# knxhome-lqfp48.net
KiCad netlist of a schematic drawn in EAGLE
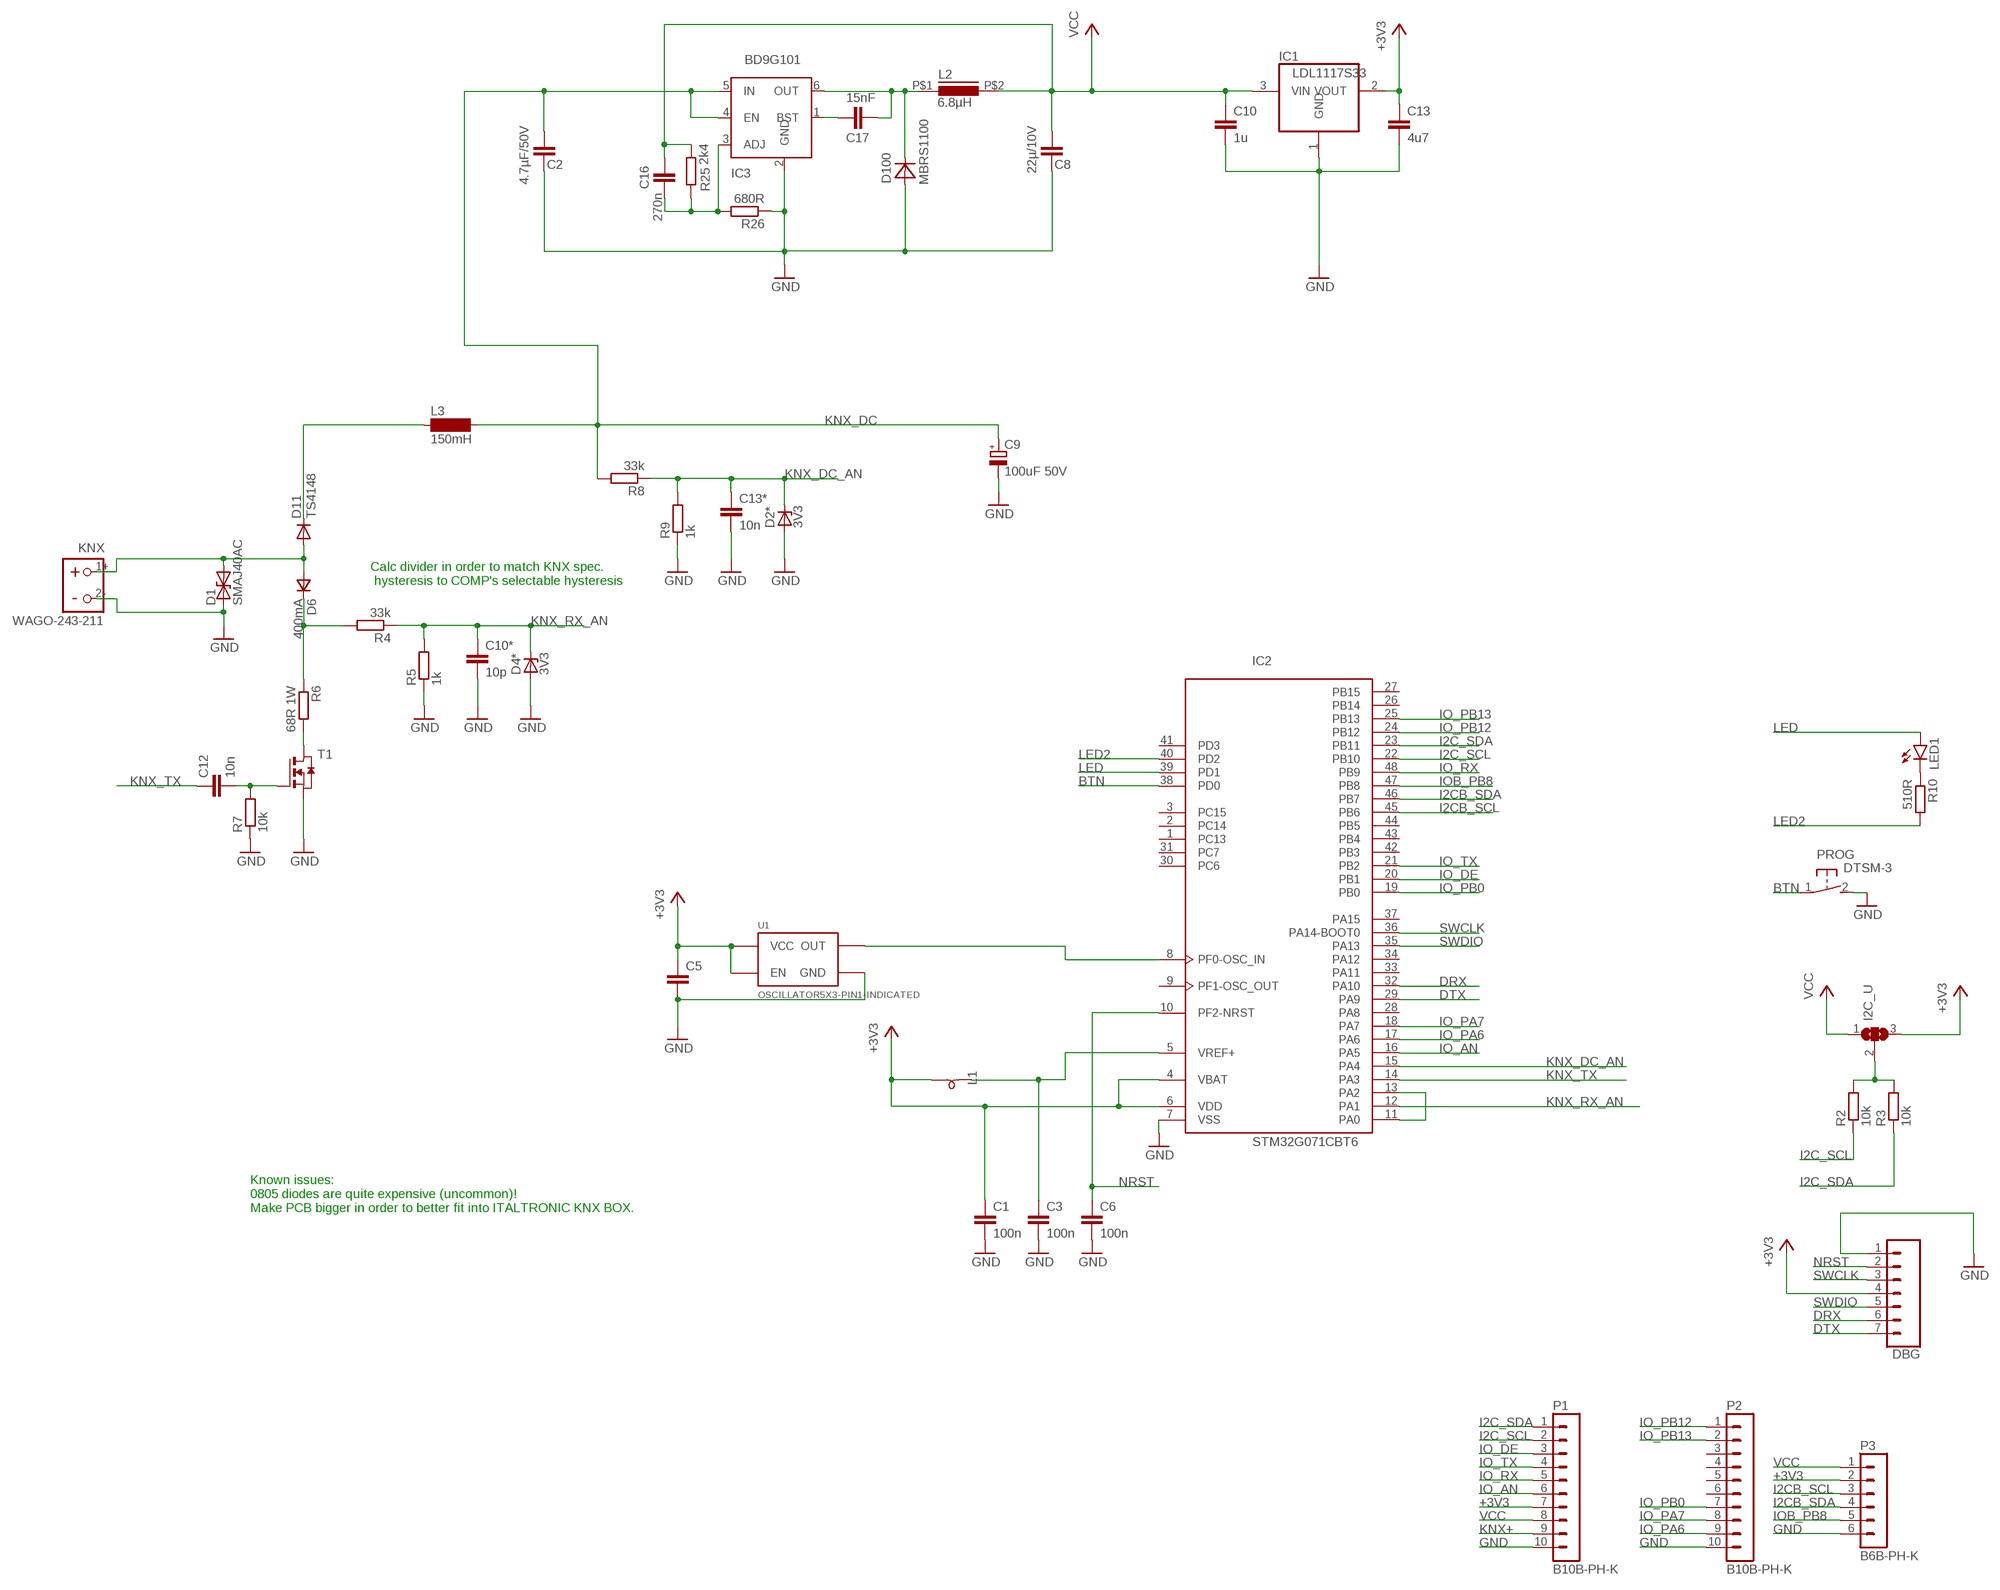
[diagram p0: schematic, sheet 1]

(export (version "E")
  (design (tool "Eeschema 10.0.6"))
  (components
    (comp (ref "C1")
      (value "100n")
      (footprint "eagle-import:C0805")
      (libsource (lib "eagle-import") (part "C-EUC0805"))
    )
    (comp (ref "C2")
      (value "4.7µF/50V")
      (footprint "eagle-import:C0805")
      (libsource (lib "eagle-import") (part "C-EUC0805"))
    )
    (comp (ref "C3")
      (value "100n")
      (footprint "eagle-import:C0805")
      (libsource (lib "eagle-import") (part "C-EUC0805"))
    )
    (comp (ref "C5")
      (value "C-EUC0805")
      (footprint "eagle-import:C0805")
      (libsource (lib "eagle-import") (part "C-EUC0805"))
    )
    (comp (ref "C6")
      (value "100n")
      (footprint "eagle-import:C0805")
      (libsource (lib "eagle-import") (part "C-EUC0805"))
    )
    (comp (ref "C8")
      (value "22µ/10V")
      (footprint "eagle-import:C0805")
      (libsource (lib "eagle-import") (part "C-EUC0805"))
    )
    (comp (ref "C9")
      (value "100uF 50V")
      (footprint "eagle-import:E3,5-8")
      (libsource (lib "eagle-import") (part "CPOL-EUE3.5-8"))
    )
    (comp (ref "C10")
      (value "1u")
      (footprint "eagle-import:C0805")
      (libsource (lib "eagle-import") (part "C-EUC0805"))
    )
    (comp (ref "C10*")
      (value "10p")
      (footprint "eagle-import:C0805")
      (libsource (lib "eagle-import") (part "C-EUC0805"))
    )
    (comp (ref "C12")
      (value "10n")
      (footprint "eagle-import:C0805")
      (libsource (lib "eagle-import") (part "C-EUC0805"))
    )
    (comp (ref "C13")
      (value "4u7")
      (footprint "eagle-import:C0805")
      (libsource (lib "eagle-import") (part "C-EUC0805"))
    )
    (comp (ref "C13*")
      (value "10n")
      (footprint "eagle-import:C0805")
      (libsource (lib "eagle-import") (part "C-EUC0805"))
    )
    (comp (ref "C16")
      (value "270n")
      (footprint "eagle-import:C0805")
      (libsource (lib "eagle-import") (part "C-EUC0805"))
    )
    (comp (ref "C17")
      (value "15nF")
      (footprint "eagle-import:C0805")
      (libsource (lib "eagle-import") (part "C-EUC0805"))
    )
    (comp (ref "D1")
      (value "SMAJ40AC")
      (footprint "eagle-import:DO-214AC")
      (libsource (lib "eagle-import") (part "SMAJ40AC"))
    )
    (comp (ref "D2*")
      (value "3V3")
      (footprint "eagle-import:SOT23")
      (libsource (lib "eagle-import") (part "ZENER-DIODESOT23"))
    )
    (comp (ref "D4*")
      (value "3V3")
      (footprint "eagle-import:SOT23")
      (libsource (lib "eagle-import") (part "ZENER-DIODESOT23"))
    )
    (comp (ref "D6")
      (value "400mA")
      (footprint "eagle-import:SOD323")
      (fields (field (name "MPN") "CDSOD323-T05C"))
      (libsource (lib "eagle-import") (part "DSOD323"))
    )
    (comp (ref "D11")
      (value "TS4148")
      (footprint "eagle-import:D0805")
      (libsource (lib "eagle-import") (part "DIODE-D0805"))
    )
    (comp (ref "D100")
      (value "MBRS1100")
      (footprint "eagle-import:SMA")
      (libsource (lib "eagle-import") (part "MBRA340T3"))
    )
    (comp (ref "DBG")
      (value "CONN_07LOCK")
      (footprint "eagle-import:1X07_LOCK")
      (libsource (lib "eagle-import") (part "CONN_07LOCK"))
    )
    (comp (ref "I2C_U")
      (value "SJ2W")
      (footprint "eagle-import:SJ_2")
      (libsource (lib "eagle-import") (part "SJ2W"))
    )
    (comp (ref "IC1")
      (value "LDL1117S33")
      (footprint "eagle-import:SOT223")
      (fields (field (name "MPN") "REG1117"))
      (libsource (lib "eagle-import") (part "REG1117"))
    )
    (comp (ref "IC2")
      (value "STM32G071CBT6")
      (footprint "eagle-import:LQFP48")
      (libsource (lib "eagle-import") (part "STM32G071CBT6"))
    )
    (comp (ref "IC3")
      (value "BD9G101")
      (footprint "eagle-import:SOT23-6")
      (libsource (lib "eagle-import") (part "BD9G101GBD9G101G-SOT23-6"))
    )
    (comp (ref "KNX")
      (value "WAGO-243-211")
      (footprint "eagle-import:WAGO-243-211")
      (libsource (lib "eagle-import") (part "WAGO-243-211"))
    )
    (comp (ref "L1")
      (value "FERRITE BEAD")
      (footprint "eagle-import:SM-B5")
      (libsource (lib "eagle-import") (part "SM-B5"))
    )
    (comp (ref "L2")
      (value "6.8µH")
      (footprint "eagle-import:PIS2812")
      (libsource (lib "eagle-import") (part "IND_FASTRON_1616FPS"))
    )
    (comp (ref "L3")
      (value "150mH")
      (footprint "eagle-import:BS11_LIEGEND")
      (libsource (lib "eagle-import") (part "SD12BS11_LIEGEND"))
    )
    (comp (ref "LED1")
      (value "LEDCHIP-LED0805")
      (footprint "eagle-import:CHIP-LED0805")
      (libsource (lib "eagle-import") (part "LEDCHIP-LED0805"))
    )
    (comp (ref "P1")
      (value "B10B-PH-K")
      (footprint "eagle-import:B10B-PH-K")
      (libsource (lib "eagle-import") (part "B10B-PH-K"))
    )
    (comp (ref "P2")
      (value "B10B-PH-K")
      (footprint "eagle-import:B10B-PH-K")
      (libsource (lib "eagle-import") (part "B10B-PH-K"))
    )
    (comp (ref "P3")
      (value "B6B-PH-K")
      (footprint "eagle-import:B6B-PH-K")
      (libsource (lib "eagle-import") (part "B6B-PH-K"))
    )
    (comp (ref "PROG")
      (value "DTSM-3")
      (footprint "eagle-import:DTSM-3")
      (libsource (lib "eagle-import") (part "DTSM-3"))
    )
    (comp (ref "R2")
      (value "10k")
      (footprint "eagle-import:R0805")
      (libsource (lib "eagle-import") (part "R-EU_R0805"))
    )
    (comp (ref "R3")
      (value "10k")
      (footprint "eagle-import:R0805")
      (libsource (lib "eagle-import") (part "R-EU_R0805"))
    )
    (comp (ref "R4")
      (value "33k")
      (footprint "eagle-import:R0805")
      (libsource (lib "eagle-import") (part "R-EU_R0805"))
    )
    (comp (ref "R5")
      (value "1k")
      (footprint "eagle-import:R0805")
      (libsource (lib "eagle-import") (part "R-EU_R0805"))
    )
    (comp (ref "R6")
      (value "68R 1W")
      (footprint "eagle-import:R2512")
      (libsource (lib "eagle-import") (part "R-EU_R2512"))
    )
    (comp (ref "R7")
      (value "10k")
      (footprint "eagle-import:R0805")
      (libsource (lib "eagle-import") (part "R-EU_R0805"))
    )
    (comp (ref "R8")
      (value "33k")
      (footprint "eagle-import:R0805")
      (libsource (lib "eagle-import") (part "R-EU_R0805"))
    )
    (comp (ref "R9")
      (value "1k")
      (footprint "eagle-import:R0805")
      (libsource (lib "eagle-import") (part "R-EU_R0805"))
    )
    (comp (ref "R10")
      (value "510R")
      (footprint "eagle-import:R0805")
      (libsource (lib "eagle-import") (part "R-EU_R0805"))
    )
    (comp (ref "R25")
      (value "2k4")
      (footprint "eagle-import:R0805")
      (libsource (lib "eagle-import") (part "R-EU_R0805"))
    )
    (comp (ref "R26")
      (value "680R")
      (footprint "eagle-import:R0805")
      (libsource (lib "eagle-import") (part "R-EU_R0805"))
    )
    (comp (ref "T1")
      (value "NMOSSOT23")
      (footprint "eagle-import:SOT-23")
      (libsource (lib "eagle-import") (part "NMOSSOT23"))
    )
    (comp (ref "U1")
      (value "OSCILLATOR5X3-PIN1-INDICATED")
      (footprint "eagle-import:CRYSTAL-OSC-SMD-5X3")
      (libsource (lib "eagle-import") (part "OSCILLATOR5X3-PIN1-INDICATED"))
    )
  )
  (nets
    (net (code "1") (name "+3V3") (class "Default")
      (node (ref "C1") (pin "1") (pinfunction "1_1") (pintype "passive"))
      (node (ref "C13") (pin "1") (pinfunction "1_1") (pintype "passive"))
      (node (ref "C5") (pin "1") (pinfunction "1_1") (pintype "passive"))
      (node (ref "DBG") (pin "4") (pinfunction "4_4") (pintype "passive"))
      (node (ref "I2C_U") (pin "3") (pinfunction "3_3") (pintype "passive"))
      (node (ref "IC1") (pin "2") (pinfunction "VOUT_2") (pintype "output"))
      (node (ref "IC2") (pin "4") (pinfunction "VBAT_4") (pintype "power_in"))
      (node (ref "IC2") (pin "6") (pinfunction "VDD_6") (pintype "power_in"))
      (node (ref "L1") (pin "1") (pinfunction "1_1") (pintype "passive"))
      (node (ref "P1") (pin "7") (pinfunction "7_7") (pintype "passive"))
      (node (ref "P3") (pin "2") (pinfunction "2_2") (pintype "passive"))
      (node (ref "U1") (pin "1") (pinfunction "EN_1") (pintype "bidirectional"))
      (node (ref "U1") (pin "4") (pinfunction "VCC_4") (pintype "bidirectional"))
    )
    (net (code "2") (name "/BTN") (class "Default")
      (node (ref "IC2") (pin "38") (pinfunction "PD0_38") (pintype "bidirectional"))
      (node (ref "PROG") (pin "1") (pinfunction "1_1") (pintype "passive"))
    )
    (net (code "3") (name "/DRX") (class "Default")
      (node (ref "DBG") (pin "6") (pinfunction "6_6") (pintype "passive"))
      (node (ref "IC2") (pin "32") (pinfunction "PA10_32") (pintype "bidirectional"))
    )
    (net (code "4") (name "/DTX") (class "Default")
      (node (ref "DBG") (pin "7") (pinfunction "7_7") (pintype "passive"))
      (node (ref "IC2") (pin "29") (pinfunction "PA9_29") (pintype "bidirectional"))
    )
    (net (code "5") (name "/I2CB_SCL") (class "Default")
      (node (ref "IC2") (pin "45") (pinfunction "PB6_45") (pintype "bidirectional"))
      (node (ref "P3") (pin "3") (pinfunction "3_3") (pintype "passive"))
    )
    (net (code "6") (name "/I2CB_SDA") (class "Default")
      (node (ref "IC2") (pin "46") (pinfunction "PB7_46") (pintype "bidirectional"))
      (node (ref "P3") (pin "4") (pinfunction "4_4") (pintype "passive"))
    )
    (net (code "7") (name "/I2C_SCL") (class "Default")
      (node (ref "IC2") (pin "22") (pinfunction "PB10_22") (pintype "bidirectional"))
      (node (ref "P1") (pin "2") (pinfunction "2_2") (pintype "passive"))
      (node (ref "R2") (pin "1") (pinfunction "1_1") (pintype "passive"))
    )
    (net (code "8") (name "/I2C_SDA") (class "Default")
      (node (ref "IC2") (pin "23") (pinfunction "PB11_23") (pintype "bidirectional"))
      (node (ref "P1") (pin "1") (pinfunction "1_1") (pintype "passive"))
      (node (ref "R3") (pin "1") (pinfunction "1_1") (pintype "passive"))
    )
    (net (code "9") (name "/IOB_PB8") (class "Default")
      (node (ref "IC2") (pin "47") (pinfunction "PB8_47") (pintype "bidirectional"))
      (node (ref "P3") (pin "5") (pinfunction "5_5") (pintype "passive"))
    )
    (net (code "10") (name "/IO_AN") (class "Default")
      (node (ref "IC2") (pin "16") (pinfunction "PA5_16") (pintype "bidirectional"))
      (node (ref "P1") (pin "6") (pinfunction "6_6") (pintype "passive"))
    )
    (net (code "11") (name "/IO_DE") (class "Default")
      (node (ref "IC2") (pin "20") (pinfunction "PB1_20") (pintype "bidirectional"))
      (node (ref "P1") (pin "3") (pinfunction "3_3") (pintype "passive"))
    )
    (net (code "12") (name "/IO_PA6") (class "Default")
      (node (ref "IC2") (pin "17") (pinfunction "PA6_17") (pintype "bidirectional"))
      (node (ref "P2") (pin "9") (pinfunction "9_9") (pintype "passive"))
    )
    (net (code "13") (name "/IO_PA7") (class "Default")
      (node (ref "IC2") (pin "18") (pinfunction "PA7_18") (pintype "bidirectional"))
      (node (ref "P2") (pin "8") (pinfunction "8_8") (pintype "passive"))
    )
    (net (code "14") (name "/IO_PB0") (class "Default")
      (node (ref "IC2") (pin "19") (pinfunction "PB0_19") (pintype "bidirectional"))
      (node (ref "P2") (pin "7") (pinfunction "7_7") (pintype "passive"))
    )
    (net (code "15") (name "/IO_PB12") (class "Default")
      (node (ref "IC2") (pin "24") (pinfunction "PB12_24") (pintype "bidirectional"))
      (node (ref "P2") (pin "1") (pinfunction "1_1") (pintype "passive"))
    )
    (net (code "16") (name "/IO_PB13") (class "Default")
      (node (ref "IC2") (pin "25") (pinfunction "PB13_25") (pintype "bidirectional"))
      (node (ref "P2") (pin "2") (pinfunction "2_2") (pintype "passive"))
    )
    (net (code "17") (name "/IO_RX") (class "Default")
      (node (ref "IC2") (pin "48") (pinfunction "PB9_48") (pintype "bidirectional"))
      (node (ref "P1") (pin "5") (pinfunction "5_5") (pintype "passive"))
    )
    (net (code "18") (name "/IO_TX") (class "Default")
      (node (ref "IC2") (pin "21") (pinfunction "PB2_21") (pintype "bidirectional"))
      (node (ref "P1") (pin "4") (pinfunction "4_4") (pintype "passive"))
    )
    (net (code "19") (name "/KNX+") (class "Default")
      (node (ref "D1") (pin "C") (pinfunction "C_C") (pintype "passive"))
      (node (ref "D11") (pin "A") (pinfunction "A_A") (pintype "passive"))
      (node (ref "D6") (pin "2") (pinfunction "A_2") (pintype "passive"))
      (node (ref "KNX") (pin "1+") (pinfunction "1+_1+") (pintype "passive"))
      (node (ref "P1") (pin "9") (pinfunction "9_9") (pintype "passive"))
    )
    (net (code "20") (name "/KNX_DC") (class "Default")
      (node (ref "C2") (pin "2") (pinfunction "2_2") (pintype "passive"))
      (node (ref "C9") (pin "+") (pinfunction "+_+") (pintype "passive"))
      (node (ref "IC3") (pin "4") (pinfunction "EN_4") (pintype "input"))
      (node (ref "IC3") (pin "5") (pinfunction "IN_5") (pintype "input"))
      (node (ref "L3") (pin "2") (pinfunction "2_2") (pintype "passive"))
      (node (ref "R8") (pin "2") (pinfunction "2_2") (pintype "passive"))
    )
    (net (code "21") (name "/KNX_DC_AN") (class "Default")
      (node (ref "C13*") (pin "1") (pinfunction "1_1") (pintype "passive"))
      (node (ref "D2*") (pin "3") (pinfunction "C_3") (pintype "passive"))
      (node (ref "IC2") (pin "15") (pinfunction "PA4_15") (pintype "bidirectional"))
      (node (ref "R8") (pin "1") (pinfunction "1_1") (pintype "passive"))
      (node (ref "R9") (pin "2") (pinfunction "2_2") (pintype "passive"))
    )
    (net (code "22") (name "/KNX_RX_AN") (class "Default")
      (node (ref "C10*") (pin "1") (pinfunction "1_1") (pintype "passive"))
      (node (ref "D4*") (pin "3") (pinfunction "C_3") (pintype "passive"))
      (node (ref "IC2") (pin "12") (pinfunction "PA1_12") (pintype "bidirectional"))
      (node (ref "R4") (pin "1") (pinfunction "1_1") (pintype "passive"))
      (node (ref "R5") (pin "2") (pinfunction "2_2") (pintype "passive"))
    )
    (net (code "23") (name "/KNX_TX") (class "Default")
      (node (ref "C12") (pin "1") (pinfunction "1_1") (pintype "passive"))
      (node (ref "IC2") (pin "14") (pinfunction "PA3_14") (pintype "bidirectional"))
    )
    (net (code "24") (name "/LED") (class "Default")
      (node (ref "IC2") (pin "39") (pinfunction "PD1_39") (pintype "bidirectional"))
      (node (ref "LED1") (pin "A") (pinfunction "A_A") (pintype "passive"))
    )
    (net (code "25") (name "/LED2") (class "Default")
      (node (ref "IC2") (pin "40") (pinfunction "PD2_40") (pintype "bidirectional"))
      (node (ref "R10") (pin "2") (pinfunction "2_2") (pintype "passive"))
    )
    (net (code "26") (name "/NRST") (class "Default")
      (node (ref "C6") (pin "1") (pinfunction "1_1") (pintype "passive"))
      (node (ref "DBG") (pin "2") (pinfunction "2_2") (pintype "passive"))
      (node (ref "IC2") (pin "10") (pinfunction "PF2-NRST_10") (pintype "bidirectional"))
    )
    (net (code "27") (name "/SWCLK") (class "Default")
      (node (ref "DBG") (pin "3") (pinfunction "3_3") (pintype "passive"))
      (node (ref "IC2") (pin "36") (pinfunction "PA14-BOOT0_36") (pintype "bidirectional"))
    )
    (net (code "28") (name "/SWDIO") (class "Default")
      (node (ref "DBG") (pin "5") (pinfunction "5_5") (pintype "passive"))
      (node (ref "IC2") (pin "35") (pinfunction "PA13_35") (pintype "bidirectional"))
    )
    (net (code "29") (name "GND") (class "Default")
      (node (ref "C1") (pin "2") (pinfunction "2_2") (pintype "passive"))
      (node (ref "C10") (pin "2") (pinfunction "2_2") (pintype "passive"))
      (node (ref "C10*") (pin "2") (pinfunction "2_2") (pintype "passive"))
      (node (ref "C13") (pin "2") (pinfunction "2_2") (pintype "passive"))
      (node (ref "C13*") (pin "2") (pinfunction "2_2") (pintype "passive"))
      (node (ref "C2") (pin "1") (pinfunction "1_1") (pintype "passive"))
      (node (ref "C3") (pin "2") (pinfunction "2_2") (pintype "passive"))
      (node (ref "C5") (pin "2") (pinfunction "2_2") (pintype "passive"))
      (node (ref "C6") (pin "2") (pinfunction "2_2") (pintype "passive"))
      (node (ref "C8") (pin "1") (pinfunction "1_1") (pintype "passive"))
      (node (ref "C9") (pin "-") (pinfunction "-_-") (pintype "passive"))
      (node (ref "D1") (pin "A") (pinfunction "A_A") (pintype "passive"))
      (node (ref "D100") (pin "A") (pinfunction "A_A") (pintype "passive"))
      (node (ref "D2*") (pin "1") (pinfunction "A_1") (pintype "passive"))
      (node (ref "D4*") (pin "1") (pinfunction "A_1") (pintype "passive"))
      (node (ref "DBG") (pin "1") (pinfunction "1_1") (pintype "passive"))
      (node (ref "IC1") (pin "1") (pinfunction "GND_1") (pintype "power_in"))
      (node (ref "IC2") (pin "7") (pinfunction "VSS_7") (pintype "power_in"))
      (node (ref "IC3") (pin "2") (pinfunction "GND_2") (pintype "power_in"))
      (node (ref "KNX") (pin "2-") (pinfunction "2-_2-") (pintype "passive"))
      (node (ref "P1") (pin "10") (pinfunction "10_10") (pintype "passive"))
      (node (ref "P2") (pin "10") (pinfunction "10_10") (pintype "passive"))
      (node (ref "P3") (pin "6") (pinfunction "6_6") (pintype "passive"))
      (node (ref "PROG") (pin "2") (pinfunction "2_2") (pintype "passive"))
      (node (ref "R26") (pin "1") (pinfunction "1_1") (pintype "passive"))
      (node (ref "R5") (pin "1") (pinfunction "1_1") (pintype "passive"))
      (node (ref "R7") (pin "1") (pinfunction "1_1") (pintype "passive"))
      (node (ref "R9") (pin "1") (pinfunction "1_1") (pintype "passive"))
      (node (ref "T1") (pin "2") (pinfunction "S_2") (pintype "passive"))
      (node (ref "U1") (pin "2") (pinfunction "GND_2") (pintype "bidirectional"))
    )
    (net (code "30") (name "Net-(D6-C)") (class "Default")
      (node (ref "D6") (pin "1") (pinfunction "C_1") (pintype "passive"))
      (node (ref "R4") (pin "2") (pinfunction "2_2") (pintype "passive"))
      (node (ref "R6") (pin "1") (pinfunction "1_1") (pintype "passive"))
    )
    (net (code "31") (name "Net-(D11-PadC)") (class "Default")
      (node (ref "D11") (pin "C") (pinfunction "C_C") (pintype "passive"))
      (node (ref "L3") (pin "1") (pinfunction "1_1") (pintype "passive"))
    )
    (net (code "32") (name "Net-(I2C_U-Pad2)") (class "Default")
      (node (ref "I2C_U") (pin "2") (pinfunction "2_2") (pintype "passive"))
      (node (ref "R2") (pin "2") (pinfunction "2_2") (pintype "passive"))
      (node (ref "R3") (pin "2") (pinfunction "2_2") (pintype "passive"))
    )
    (net (code "33") (name "Net-(IC2-PA0)") (class "Default")
      (node (ref "IC2") (pin "11") (pinfunction "PA0_11") (pintype "bidirectional"))
      (node (ref "IC2") (pin "13") (pinfunction "PA2_13") (pintype "bidirectional"))
    )
    (net (code "34") (name "Net-(IC2-PF0-OSC_IN)") (class "Default")
      (node (ref "IC2") (pin "8") (pinfunction "PF0-OSC_IN_8") (pintype "bidirectional"))
      (node (ref "U1") (pin "3") (pinfunction "OUT_3") (pintype "bidirectional"))
    )
    (net (code "35") (name "Net-(IC2-VREF+)") (class "Default")
      (node (ref "C3") (pin "1") (pinfunction "1_1") (pintype "passive"))
      (node (ref "IC2") (pin "5") (pinfunction "VREF+_5") (pintype "input"))
      (node (ref "L1") (pin "2") (pinfunction "2_2") (pintype "passive"))
    )
    (net (code "36") (name "Net-(IC3-ADJ)") (class "Default")
      (node (ref "C16") (pin "1") (pinfunction "1_1") (pintype "passive"))
      (node (ref "IC3") (pin "3") (pinfunction "ADJ_3") (pintype "passive"))
      (node (ref "R25") (pin "1") (pinfunction "1_1") (pintype "passive"))
      (node (ref "R26") (pin "2") (pinfunction "2_2") (pintype "passive"))
    )
    (net (code "37") (name "Net-(IC3-BST)") (class "Default")
      (node (ref "C17") (pin "2") (pinfunction "2_2") (pintype "passive"))
      (node (ref "IC3") (pin "1") (pinfunction "BST_1") (pintype "output"))
    )
    (net (code "38") (name "Net-(IC3-OUT)") (class "Default")
      (node (ref "C17") (pin "1") (pinfunction "1_1") (pintype "passive"))
      (node (ref "D100") (pin "C") (pinfunction "C_C") (pintype "passive"))
      (node (ref "IC3") (pin "6") (pinfunction "OUT_6") (pintype "output"))
      (node (ref "L2") (pin "P$1") (pinfunction "1_P$1") (pintype "passive"))
    )
    (net (code "39") (name "Net-(LED1-PadC)") (class "Default")
      (node (ref "LED1") (pin "C") (pinfunction "C_C") (pintype "passive"))
      (node (ref "R10") (pin "1") (pinfunction "1_1") (pintype "passive"))
    )
    (net (code "40") (name "Net-(T1-D)") (class "Default")
      (node (ref "R6") (pin "2") (pinfunction "2_2") (pintype "passive"))
      (node (ref "T1") (pin "1") (pinfunction "D_1") (pintype "passive"))
    )
    (net (code "41") (name "Net-(T1-G)") (class "Default")
      (node (ref "C12") (pin "2") (pinfunction "2_2") (pintype "passive"))
      (node (ref "R7") (pin "2") (pinfunction "2_2") (pintype "passive"))
      (node (ref "T1") (pin "3") (pinfunction "G_3") (pintype "passive"))
    )
    (net (code "42") (name "VCC") (class "Default")
      (node (ref "C10") (pin "1") (pinfunction "1_1") (pintype "passive"))
      (node (ref "C16") (pin "2") (pinfunction "2_2") (pintype "passive"))
      (node (ref "C8") (pin "2") (pinfunction "2_2") (pintype "passive"))
      (node (ref "I2C_U") (pin "1") (pinfunction "1_1") (pintype "passive"))
      (node (ref "IC1") (pin "3") (pinfunction "VIN_3") (pintype "input"))
      (node (ref "L2") (pin "P$2") (pinfunction "2_P$2") (pintype "passive"))
      (node (ref "P1") (pin "8") (pinfunction "8_8") (pintype "passive"))
      (node (ref "P3") (pin "1") (pinfunction "1_1") (pintype "passive"))
      (node (ref "R25") (pin "2") (pinfunction "2_2") (pintype "passive"))
    )
    (net (code "43") (name "unconnected-(IC2-PA8-Pad28)") (class "Default")
      (node (ref "IC2") (pin "28") (pinfunction "PA8_28") (pintype "bidirectional"))
    )
    (net (code "44") (name "unconnected-(IC2-PA11-Pad33)") (class "Default")
      (node (ref "IC2") (pin "33") (pinfunction "PA11_33") (pintype "bidirectional"))
    )
    (net (code "45") (name "unconnected-(IC2-PA12-Pad34)") (class "Default")
      (node (ref "IC2") (pin "34") (pinfunction "PA12_34") (pintype "bidirectional"))
    )
    (net (code "46") (name "unconnected-(IC2-PA15-Pad37)") (class "Default")
      (node (ref "IC2") (pin "37") (pinfunction "PA15_37") (pintype "bidirectional"))
    )
    (net (code "47") (name "unconnected-(IC2-PB3-Pad42)") (class "Default")
      (node (ref "IC2") (pin "42") (pinfunction "PB3_42") (pintype "bidirectional"))
    )
    (net (code "48") (name "unconnected-(IC2-PB4-Pad43)") (class "Default")
      (node (ref "IC2") (pin "43") (pinfunction "PB4_43") (pintype "bidirectional"))
    )
    (net (code "49") (name "unconnected-(IC2-PB5-Pad44)") (class "Default")
      (node (ref "IC2") (pin "44") (pinfunction "PB5_44") (pintype "bidirectional"))
    )
    (net (code "50") (name "unconnected-(IC2-PB14-Pad26)") (class "Default")
      (node (ref "IC2") (pin "26") (pinfunction "PB14_26") (pintype "bidirectional"))
    )
    (net (code "51") (name "unconnected-(IC2-PB15-Pad27)") (class "Default")
      (node (ref "IC2") (pin "27") (pinfunction "PB15_27") (pintype "bidirectional"))
    )
    (net (code "52") (name "unconnected-(IC2-PC6-Pad30)") (class "Default")
      (node (ref "IC2") (pin "30") (pinfunction "PC6_30") (pintype "bidirectional"))
    )
    (net (code "53") (name "unconnected-(IC2-PC7-Pad31)") (class "Default")
      (node (ref "IC2") (pin "31") (pinfunction "PC7_31") (pintype "bidirectional"))
    )
    (net (code "54") (name "unconnected-(IC2-PC13-Pad1)") (class "Default")
      (node (ref "IC2") (pin "1") (pinfunction "PC13_1") (pintype "bidirectional"))
    )
    (net (code "55") (name "unconnected-(IC2-PC14-Pad2)") (class "Default")
      (node (ref "IC2") (pin "2") (pinfunction "PC14_2") (pintype "bidirectional"))
    )
    (net (code "56") (name "unconnected-(IC2-PC15-Pad3)") (class "Default")
      (node (ref "IC2") (pin "3") (pinfunction "PC15_3") (pintype "bidirectional"))
    )
    (net (code "57") (name "unconnected-(IC2-PD3-Pad41)") (class "Default")
      (node (ref "IC2") (pin "41") (pinfunction "PD3_41") (pintype "bidirectional"))
    )
    (net (code "58") (name "unconnected-(IC2-PF1-OSC_OUT-Pad9)") (class "Default")
      (node (ref "IC2") (pin "9") (pinfunction "PF1-OSC_OUT_9") (pintype "bidirectional"))
    )
    (net (code "59") (name "unconnected-(P2-Pad3)") (class "Default")
      (node (ref "P2") (pin "3") (pinfunction "3_3") (pintype "passive"))
    )
    (net (code "60") (name "unconnected-(P2-Pad4)") (class "Default")
      (node (ref "P2") (pin "4") (pinfunction "4_4") (pintype "passive"))
    )
    (net (code "61") (name "unconnected-(P2-Pad5)") (class "Default")
      (node (ref "P2") (pin "5") (pinfunction "5_5") (pintype "passive"))
    )
    (net (code "62") (name "unconnected-(P2-Pad6)") (class "Default")
      (node (ref "P2") (pin "6") (pinfunction "6_6") (pintype "passive"))
    )
  )
)
